# AUDIO_AMP_NB2C.net
KiCad netlist of a schematic drawn in Altium Designer
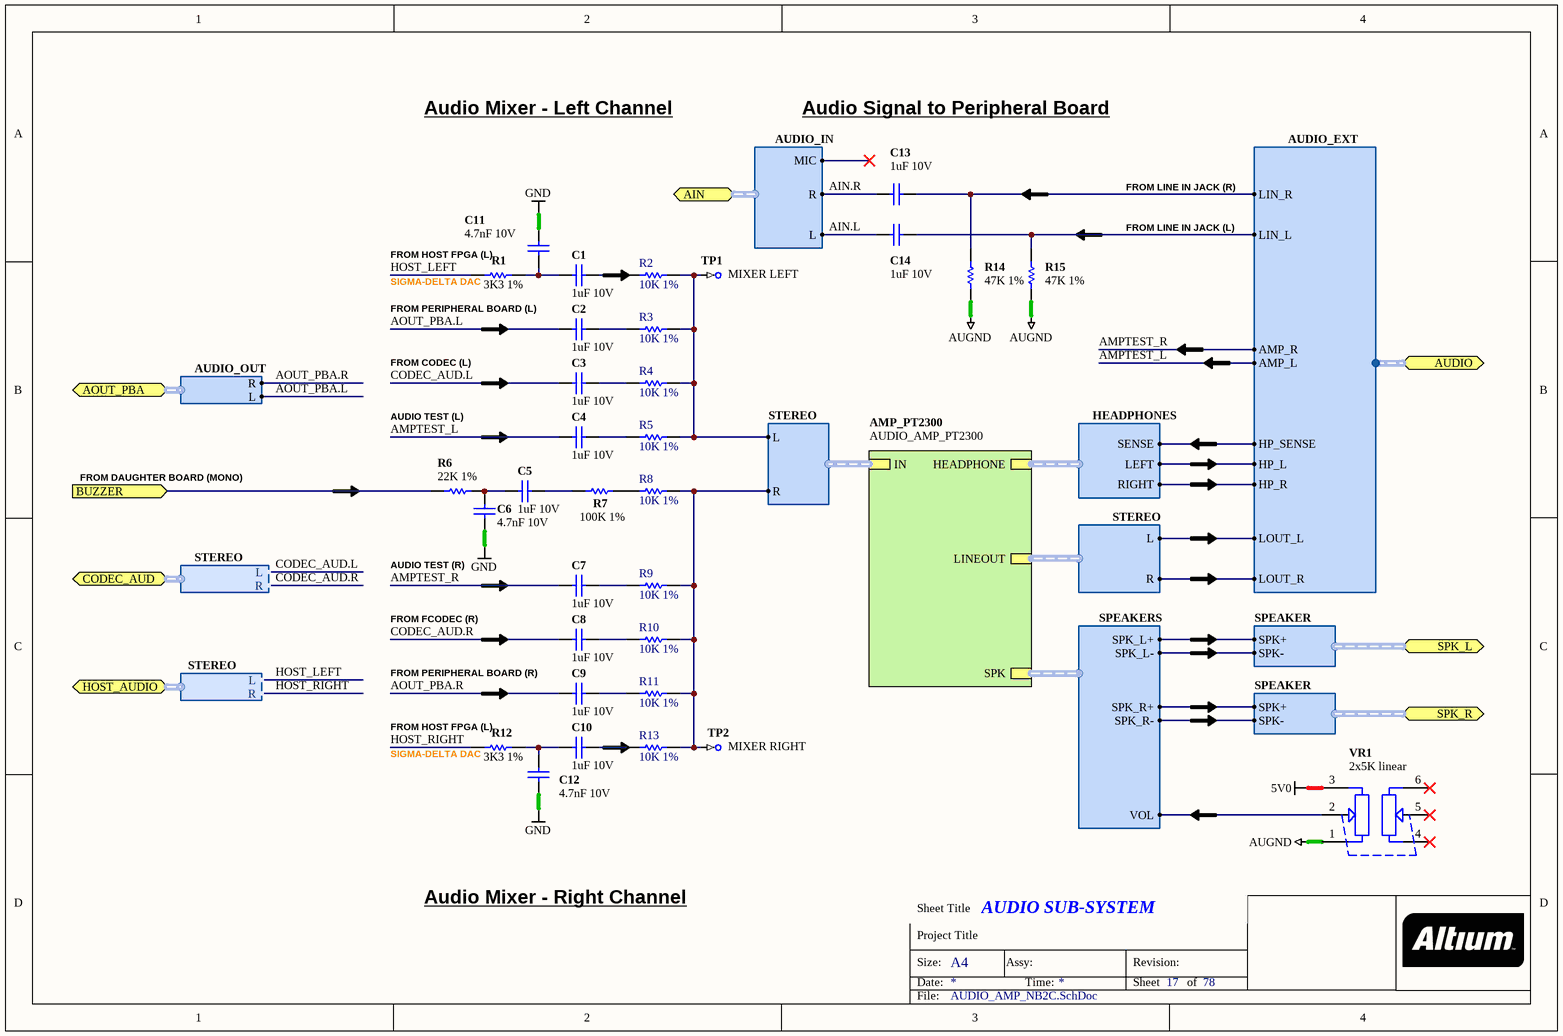
[diagram p0: AUDIO_AMP_NB2C.SchDoc]

(export (version "E")
  (design (tool "Eeschema 10.0.6"))
  (components
    (comp (ref "C1")
      (value "1uF 10V")
      (footprint "CAPC1005-STAR")
      (description "Capacitor, Ceramic, 1uF 10% 10V 0402 (1005) X5R")
      (fields (field (name "TOLERANCE") "10 %"))
      (libsource (lib "AltiumDesignLibrary") (part "CAP-NP"))
    )
    (comp (ref "C2")
      (value "1uF 10V")
      (footprint "CAPC1005-STAR")
      (description "Capacitor, Ceramic, 1uF 10% 10V 0402 (1005) X5R")
      (fields (field (name "TOLERANCE") "10 %"))
      (libsource (lib "AltiumDesignLibrary") (part "CAP-NP"))
    )
    (comp (ref "C3")
      (value "1uF 10V")
      (footprint "CAPC1005-STAR")
      (description "Capacitor, Ceramic, 1uF 10% 10V 0402 (1005) X5R")
      (fields (field (name "TOLERANCE") "10 %"))
      (libsource (lib "AltiumDesignLibrary") (part "CAP-NP"))
    )
    (comp (ref "C4")
      (value "1uF 10V")
      (footprint "CAPC1005-STAR")
      (description "Capacitor, Ceramic, 1uF 10% 10V 0402 (1005) X5R")
      (fields (field (name "TOLERANCE") "10 %"))
      (libsource (lib "AltiumDesignLibrary") (part "CAP-NP"))
    )
    (comp (ref "C5")
      (value "1uF 10V")
      (footprint "CAPC1005-STAR")
      (description "Capacitor, Ceramic, 1uF 10% 10V 0402 (1005) X5R")
      (fields (field (name "TOLERANCE") "10 %"))
      (libsource (lib "AltiumDesignLibrary") (part "CAP-NP"))
    )
    (comp (ref "C6")
      (value "4.7nF 10V")
      (footprint "CAPC1005-STAR")
      (description "Capacitor, Ceramic, 4.7nF 10% 10V 0402 (1005) X7R")
      (fields (field (name "TOLERANCE") "10 %"))
      (libsource (lib "AltiumDesignLibrary") (part "CAP-NP"))
    )
    (comp (ref "C7")
      (value "1uF 10V")
      (footprint "CAPC1005-STAR")
      (description "Capacitor, Ceramic, 1uF 10% 10V 0402 (1005) X5R")
      (fields (field (name "TOLERANCE") "10 %"))
      (libsource (lib "AltiumDesignLibrary") (part "CAP-NP"))
    )
    (comp (ref "C8")
      (value "1uF 10V")
      (footprint "CAPC1005-STAR")
      (description "Capacitor, Ceramic, 1uF 10% 10V 0402 (1005) X5R")
      (fields (field (name "TOLERANCE") "10 %"))
      (libsource (lib "AltiumDesignLibrary") (part "CAP-NP"))
    )
    (comp (ref "C9")
      (value "1uF 10V")
      (footprint "CAPC1005-STAR")
      (description "Capacitor, Ceramic, 1uF 10% 10V 0402 (1005) X5R")
      (fields (field (name "TOLERANCE") "10 %"))
      (libsource (lib "AltiumDesignLibrary") (part "CAP-NP"))
    )
    (comp (ref "C10")
      (value "1uF 10V")
      (footprint "CAPC1005-STAR")
      (description "Capacitor, Ceramic, 1uF 10% 10V 0402 (1005) X5R")
      (fields (field (name "TOLERANCE") "10 %"))
      (libsource (lib "AltiumDesignLibrary") (part "CAP-NP"))
    )
    (comp (ref "C11")
      (value "4.7nF 10V")
      (footprint "CAPC1005-STAR")
      (description "Capacitor, Ceramic, 4.7nF 10% 10V 0402 (1005) X7R")
      (fields (field (name "TOLERANCE") "10%"))
      (libsource (lib "AltiumDesignLibrary") (part "CAP-NP"))
    )
    (comp (ref "C12")
      (value "4.7nF 10V")
      (footprint "CAPC1005-STAR")
      (description "Capacitor, Ceramic, 4.7nF 10% 10V 0402 (1005) X7R")
      (fields (field (name "TOLERANCE") "10%"))
      (libsource (lib "AltiumDesignLibrary") (part "CAP-NP"))
    )
    (comp (ref "C13")
      (value "1uF 10V")
      (footprint "CAPC1005-STAR")
      (description "Capacitor, Ceramic, 1uF 10% 10V 0402 (1005) X5R")
      (fields (field (name "TOLERANCE") "10 %"))
      (libsource (lib "AltiumDesignLibrary") (part "CAP-NP"))
    )
    (comp (ref "C14")
      (value "1uF 10V")
      (footprint "CAPC1005-STAR")
      (description "Capacitor, Ceramic, 1uF 10% 10V 0402 (1005) X5R")
      (fields (field (name "TOLERANCE") "10 %"))
      (libsource (lib "AltiumDesignLibrary") (part "CAP-NP"))
    )
    (comp (ref "R1")
      (value "3K3 1%")
      (footprint "RESC1005-STAR")
      (description "Resistor, 3K3 1% 0402 (1005)")
      (fields (field (name "TOLERANCE") "1 %"))
      (libsource (lib "AltiumDesignLibrary") (part "RES"))
    )
    (comp (ref "R2")
      (value "10K 1%")
      (footprint "RESC1005-STAR")
      (description "Resistor, 10K 1% 0402 (1005)")
      (fields (field (name "TOLERANCE") "1%"))
      (libsource (lib "AltiumDesignLibrary") (part "RES"))
    )
    (comp (ref "R3")
      (value "10K 1%")
      (footprint "RESC1005-STAR")
      (description "Resistor, 10K 1% 0402 (1005)")
      (fields (field (name "TOLERANCE") "1%"))
      (libsource (lib "AltiumDesignLibrary") (part "RES"))
    )
    (comp (ref "R4")
      (value "10K 1%")
      (footprint "RESC1005-STAR")
      (description "Resistor, 10K 1% 0402 (1005)")
      (fields (field (name "TOLERANCE") "1%"))
      (libsource (lib "AltiumDesignLibrary") (part "RES"))
    )
    (comp (ref "R5")
      (value "10K 1%")
      (footprint "RESC1005-STAR")
      (description "Resistor, 10K 1% 0402 (1005)")
      (fields (field (name "TOLERANCE") "1%"))
      (libsource (lib "AltiumDesignLibrary") (part "RES"))
    )
    (comp (ref "R6")
      (value "22K 1%")
      (footprint "RESC1005-STAR")
      (description "Resistor, 22K 1% 0402 (1005)")
      (fields (field (name "TOLERANCE") "1 %"))
      (libsource (lib "altium-import") (part "root_1_RES_"))
    )
    (comp (ref "R7")
      (value "100K 1%")
      (footprint "RESC1005-STAR")
      (description "Resistor, 100K 1% 0402 (1005)")
      (fields (field (name "TOLERANCE") "1 %"))
      (libsource (lib "altium-import") (part "root_1_RES_"))
    )
    (comp (ref "R8")
      (value "10K 1%")
      (footprint "RESC1005-STAR")
      (description "Resistor, 10K 1% 0402 (1005)")
      (fields (field (name "TOLERANCE") "1%"))
      (libsource (lib "AltiumDesignLibrary") (part "RES"))
    )
    (comp (ref "R9")
      (value "10K 1%")
      (footprint "RESC1005-STAR")
      (description "Resistor, 10K 1% 0402 (1005)")
      (fields (field (name "TOLERANCE") "1%"))
      (libsource (lib "AltiumDesignLibrary") (part "RES"))
    )
    (comp (ref "R10")
      (value "10K 1%")
      (footprint "RESC1005-STAR")
      (description "Resistor, 10K 1% 0402 (1005)")
      (fields (field (name "TOLERANCE") "1%"))
      (libsource (lib "AltiumDesignLibrary") (part "RES"))
    )
    (comp (ref "R11")
      (value "10K 1%")
      (footprint "RESC1005-STAR")
      (description "Resistor, 10K 1% 0402 (1005)")
      (fields (field (name "TOLERANCE") "1%"))
      (libsource (lib "AltiumDesignLibrary") (part "RES"))
    )
    (comp (ref "R12")
      (value "3K3 1%")
      (footprint "RESC1005-STAR")
      (description "Resistor, 3K3 1% 0402 (1005)")
      (fields (field (name "TOLERANCE") "1 %"))
      (libsource (lib "AltiumDesignLibrary") (part "RES"))
    )
    (comp (ref "R13")
      (value "10K 1%")
      (footprint "RESC1005-STAR")
      (description "Resistor, 10K 1% 0402 (1005)")
      (fields (field (name "TOLERANCE") "1%"))
      (libsource (lib "AltiumDesignLibrary") (part "RES"))
    )
    (comp (ref "R14")
      (value "47K 1%")
      (footprint "RESC1005-STAR")
      (description "Resistor, 47K 1% 0402 (1005)")
      (fields (field (name "TOLERANCE") "1 %"))
      (libsource (lib "altium-import") (part "root_2_RES_"))
    )
    (comp (ref "R15")
      (value "47K 1%")
      (footprint "RESC1005-STAR")
      (description "Resistor, 47K 1% 0402 (1005)")
      (fields (field (name "TOLERANCE") "1 %"))
      (libsource (lib "altium-import") (part "root_2_RES_"))
    )
    (comp (ref "TP1")
      (value "MIXER LEFT")
      (footprint "TestPin")
      (description "Test Point, PCB Mount with Silkscreen Box")
      (libsource (lib "AltiumDesignLibrary") (part "TestPin"))
    )
    (comp (ref "TP2")
      (value "MIXER RIGHT")
      (footprint "TestPin")
      (description "Test Point, PCB Mount with Silkscreen Box")
      (libsource (lib "AltiumDesignLibrary") (part "TestPin"))
    )
    (comp (ref "VR1")
      (value "2x5K linear")
      (footprint "POT-R0911G-A1")
      (description "Potentiometer, 2 x 5K Linear 9mm PCB Mount Fluted Shaft")
      (libsource (lib "AltiumDesignLibrary") (part "POT-DUAL_GANG"))
    )
  )
  (nets
    (net (code "8") (name "/AIN.L") (class "Default")
      (node (ref "C14") (pin "2") (pinfunction "2_2") (pintype "passive"))
    )
    (net (code "9") (name "/AIN.R") (class "Default")
      (node (ref "C13") (pin "2") (pinfunction "2_2") (pintype "passive"))
    )
    (net (code "10") (name "/AMPTEST_L") (class "Default")
      (node (ref "C4") (pin "2") (pinfunction "2_2") (pintype "passive"))
    )
    (net (code "11") (name "/AMPTEST_R") (class "Default")
      (node (ref "C7") (pin "2") (pinfunction "2_2") (pintype "passive"))
    )
    (net (code "12") (name "/AOUT_PBA.L") (class "Default")
      (node (ref "C2") (pin "2") (pinfunction "2_2") (pintype "passive"))
    )
    (net (code "13") (name "/AOUT_PBA.R") (class "Default")
      (node (ref "C9") (pin "2") (pinfunction "2_2") (pintype "passive"))
    )
    (net (code "14") (name "/BUZZER") (class "Default")
      (node (ref "R6") (pin "1") (pinfunction "1_1") (pintype "passive"))
    )
    (net (code "15") (name "/CODEC_AUD.L") (class "Default")
      (node (ref "C3") (pin "2") (pinfunction "2_2") (pintype "passive"))
    )
    (net (code "16") (name "/CODEC_AUD.R") (class "Default")
      (node (ref "C8") (pin "2") (pinfunction "2_2") (pintype "passive"))
    )
    (net (code "17") (name "/HOST_LEFT") (class "Default")
      (node (ref "R1") (pin "1") (pinfunction "1_1") (pintype "passive"))
    )
    (net (code "18") (name "/HOST_RIGHT") (class "Default")
      (node (ref "R12") (pin "1") (pinfunction "1_1") (pintype "passive"))
    )
    (net (code "22") (name "/LIN_L") (class "Default")
      (node (ref "C14") (pin "1") (pinfunction "1_1") (pintype "passive"))
      (node (ref "R15") (pin "2") (pinfunction "2_2") (pintype "passive"))
    )
    (net (code "23") (name "/LIN_R") (class "Default")
      (node (ref "C13") (pin "1") (pinfunction "1_1") (pintype "passive"))
      (node (ref "R14") (pin "2") (pinfunction "2_2") (pintype "passive"))
    )
    (net (code "31") (name "/VOL") (class "Default")
      (node (ref "VR1") (pin "2") (pinfunction "2_2") (pintype "passive"))
    )
    (net (code "39") (name "5V0") (class "Default")
      (node (ref "VR1") (pin "3") (pinfunction "3_3") (pintype "passive"))
    )
    (net (code "40") (name "AUGND") (class "Default")
      (node (ref "R14") (pin "1") (pinfunction "1_1") (pintype "passive"))
      (node (ref "R15") (pin "1") (pinfunction "1_1") (pintype "passive"))
      (node (ref "VR1") (pin "1") (pinfunction "1_1") (pintype "passive"))
    )
    (net (code "41") (name "GND") (class "Default")
      (node (ref "C11") (pin "2") (pinfunction "2_2") (pintype "passive"))
      (node (ref "C12") (pin "2") (pinfunction "2_2") (pintype "passive"))
      (node (ref "C6") (pin "2") (pinfunction "2_2") (pintype "passive"))
    )
    (net (code "42") (name "Net-(C1-Pad1)") (class "Default")
      (node (ref "C1") (pin "1") (pinfunction "1_1") (pintype "passive"))
      (node (ref "R2") (pin "1") (pinfunction "1_1") (pintype "passive"))
    )
    (net (code "43") (name "Net-(C1-Pad2)") (class "Default")
      (node (ref "C1") (pin "2") (pinfunction "2_2") (pintype "passive"))
      (node (ref "C11") (pin "1") (pinfunction "1_1") (pintype "passive"))
      (node (ref "R1") (pin "2") (pinfunction "2_2") (pintype "passive"))
    )
    (net (code "44") (name "Net-(C2-Pad1)") (class "Default")
      (node (ref "C2") (pin "1") (pinfunction "1_1") (pintype "passive"))
      (node (ref "R3") (pin "1") (pinfunction "1_1") (pintype "passive"))
    )
    (net (code "45") (name "Net-(C3-Pad1)") (class "Default")
      (node (ref "C3") (pin "1") (pinfunction "1_1") (pintype "passive"))
      (node (ref "R4") (pin "1") (pinfunction "1_1") (pintype "passive"))
    )
    (net (code "46") (name "Net-(C4-Pad1)") (class "Default")
      (node (ref "C4") (pin "1") (pinfunction "1_1") (pintype "passive"))
      (node (ref "R5") (pin "1") (pinfunction "1_1") (pintype "passive"))
    )
    (net (code "47") (name "Net-(C5-Pad1)") (class "Default")
      (node (ref "C5") (pin "1") (pinfunction "1_1") (pintype "passive"))
      (node (ref "R7") (pin "1") (pinfunction "1_1") (pintype "passive"))
    )
    (net (code "48") (name "Net-(C5-Pad2)") (class "Default")
      (node (ref "C5") (pin "2") (pinfunction "2_2") (pintype "passive"))
      (node (ref "C6") (pin "1") (pinfunction "1_1") (pintype "passive"))
      (node (ref "R6") (pin "2") (pinfunction "2_2") (pintype "passive"))
    )
    (net (code "49") (name "Net-(C7-Pad1)") (class "Default")
      (node (ref "C7") (pin "1") (pinfunction "1_1") (pintype "passive"))
      (node (ref "R9") (pin "1") (pinfunction "1_1") (pintype "passive"))
    )
    (net (code "50") (name "Net-(C8-Pad1)") (class "Default")
      (node (ref "C8") (pin "1") (pinfunction "1_1") (pintype "passive"))
      (node (ref "R10") (pin "1") (pinfunction "1_1") (pintype "passive"))
    )
    (net (code "51") (name "Net-(C9-Pad1)") (class "Default")
      (node (ref "C9") (pin "1") (pinfunction "1_1") (pintype "passive"))
      (node (ref "R11") (pin "1") (pinfunction "1_1") (pintype "passive"))
    )
    (net (code "52") (name "Net-(C10-Pad1)") (class "Default")
      (node (ref "C10") (pin "1") (pinfunction "1_1") (pintype "passive"))
      (node (ref "R13") (pin "1") (pinfunction "1_1") (pintype "passive"))
    )
    (net (code "53") (name "Net-(C10-Pad2)") (class "Default")
      (node (ref "C10") (pin "2") (pinfunction "2_2") (pintype "passive"))
      (node (ref "C12") (pin "1") (pinfunction "1_1") (pintype "passive"))
      (node (ref "R12") (pin "2") (pinfunction "2_2") (pintype "passive"))
    )
    (net (code "54") (name "Net-(R2-Pad2)") (class "Default")
      (node (ref "R2") (pin "2") (pinfunction "2_2") (pintype "passive"))
      (node (ref "R3") (pin "2") (pinfunction "2_2") (pintype "passive"))
      (node (ref "R4") (pin "2") (pinfunction "2_2") (pintype "passive"))
      (node (ref "R5") (pin "2") (pinfunction "2_2") (pintype "passive"))
      (node (ref "TP1") (pin "1") (pinfunction "1_1") (pintype "input"))
    )
    (net (code "55") (name "Net-(R7-Pad2)") (class "Default")
      (node (ref "R7") (pin "2") (pinfunction "2_2") (pintype "passive"))
      (node (ref "R8") (pin "1") (pinfunction "1_1") (pintype "passive"))
    )
    (net (code "56") (name "Net-(R10-Pad2)") (class "Default")
      (node (ref "R10") (pin "2") (pinfunction "2_2") (pintype "passive"))
      (node (ref "R11") (pin "2") (pinfunction "2_2") (pintype "passive"))
      (node (ref "R13") (pin "2") (pinfunction "2_2") (pintype "passive"))
      (node (ref "R8") (pin "2") (pinfunction "2_2") (pintype "passive"))
      (node (ref "R9") (pin "2") (pinfunction "2_2") (pintype "passive"))
      (node (ref "TP2") (pin "1") (pinfunction "1_1") (pintype "input"))
    )
    (net (code "57") (name "unconnected-(VR1-Pad4)") (class "Default")
      (node (ref "VR1") (pin "4") (pinfunction "4_4") (pintype "passive+no_connect"))
    )
    (net (code "58") (name "unconnected-(VR1-Pad5)") (class "Default")
      (node (ref "VR1") (pin "5") (pinfunction "5_5") (pintype "passive+no_connect"))
    )
    (net (code "59") (name "unconnected-(VR1-Pad6)") (class "Default")
      (node (ref "VR1") (pin "6") (pinfunction "6_6") (pintype "passive+no_connect"))
    )
  )
)
